# slave.net
KiCad netlist of a schematic drawn in EAGLE
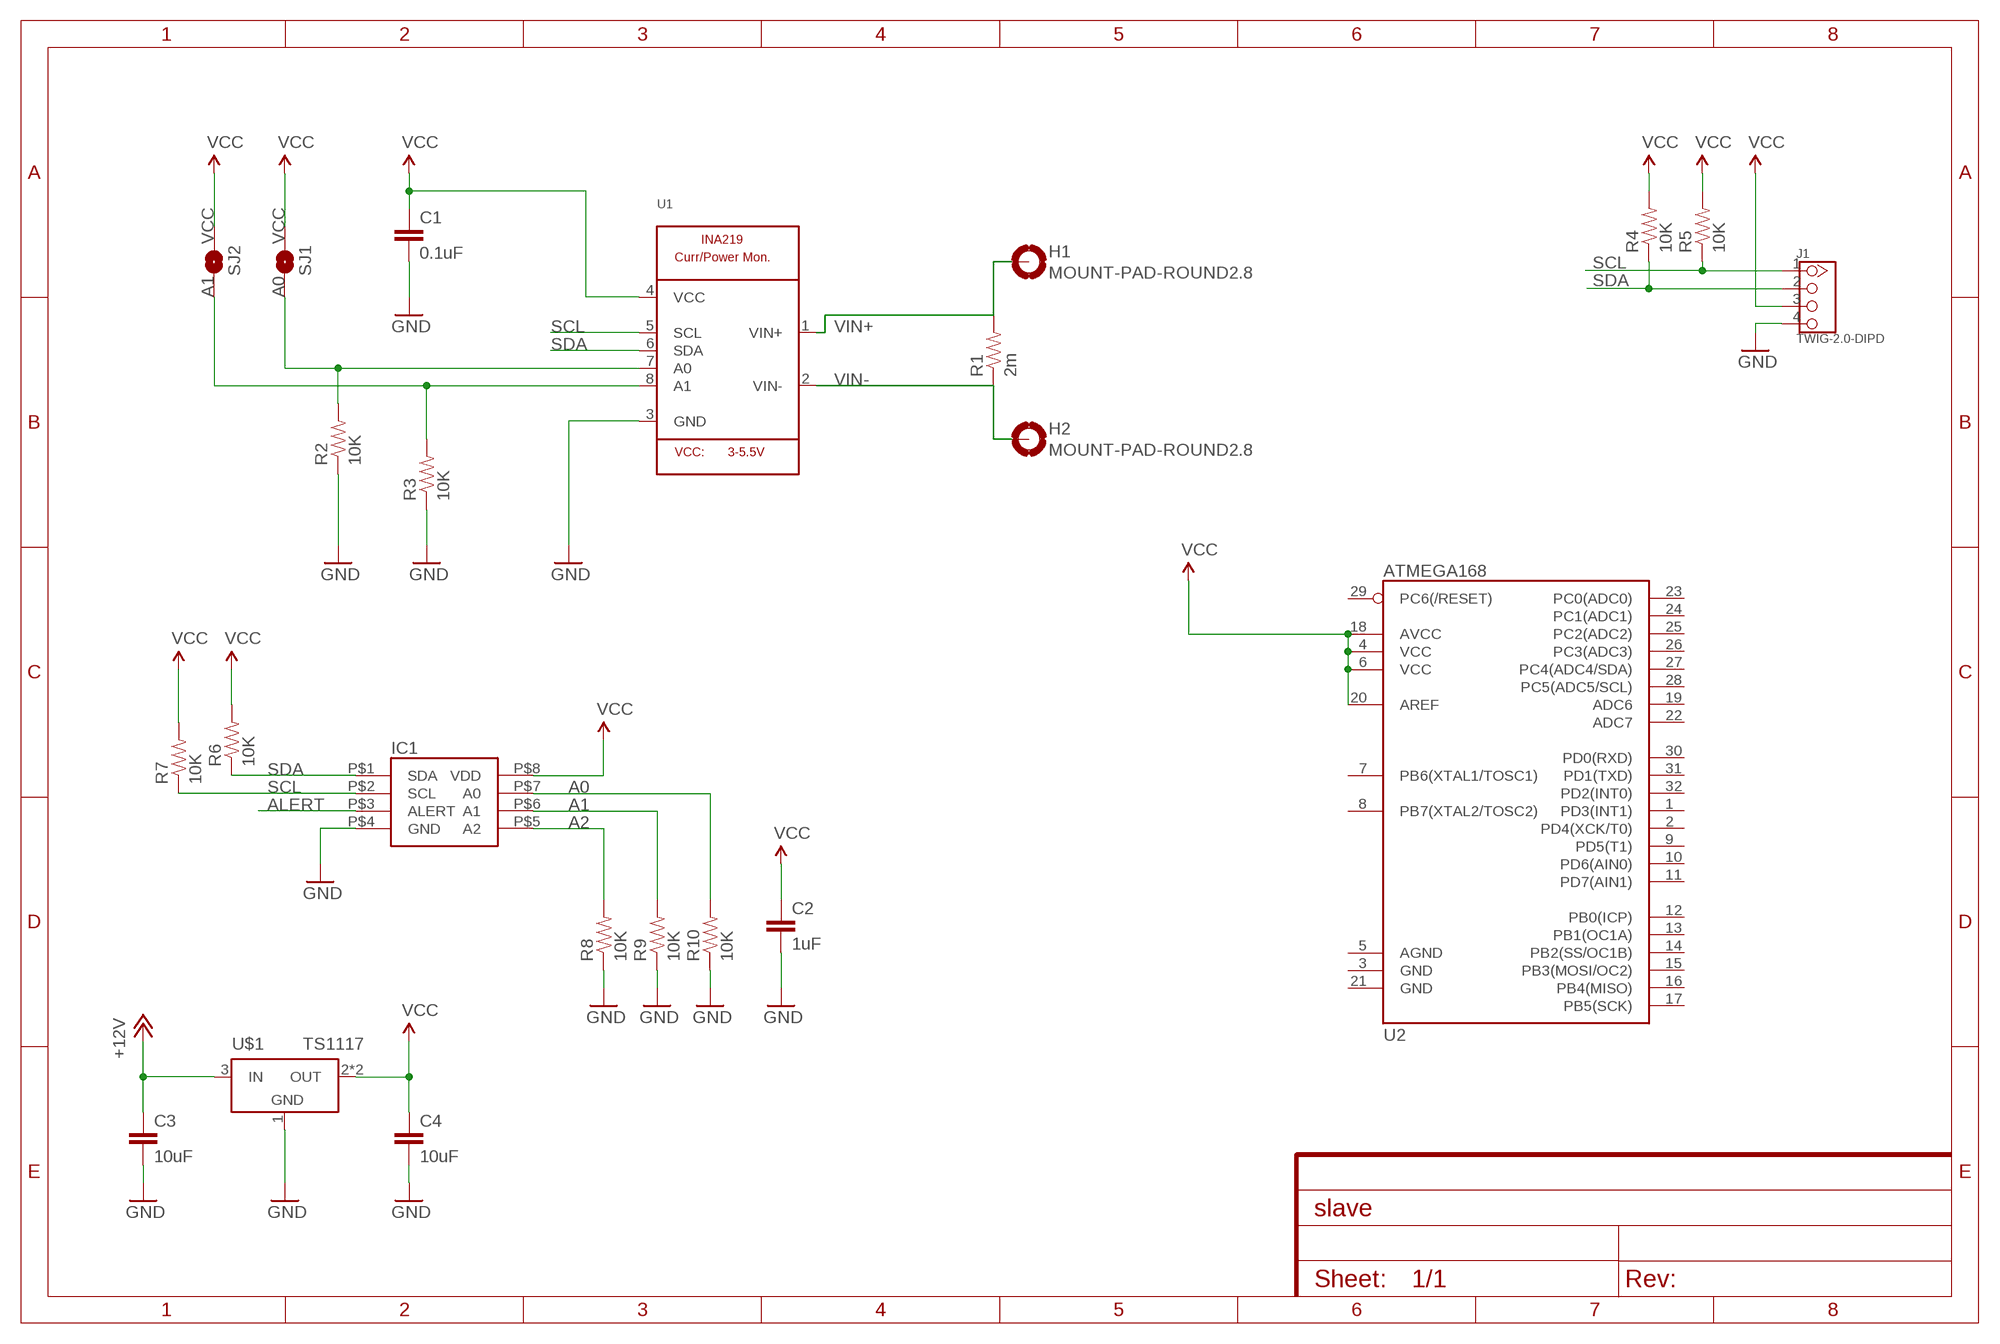
[diagram p0: schematic, sheet 1]

(export (version "E")
  (design (tool "Eeschema 10.0.6"))
  (components
    (comp (ref "C1")
      (value "0.1uF")
      (footprint "eagle-import:0805")
      (libsource (lib "eagle-import") (part "CAP0805"))
    )
    (comp (ref "C2")
      (value "1uF")
      (footprint "eagle-import:0805")
      (libsource (lib "eagle-import") (part "CAP0805"))
    )
    (comp (ref "C3")
      (value "10uF")
      (footprint "eagle-import:0805")
      (libsource (lib "eagle-import") (part "CAP0805"))
    )
    (comp (ref "C4")
      (value "10uF")
      (footprint "eagle-import:0805")
      (libsource (lib "eagle-import") (part "CAP0805"))
    )
    (comp (ref "H1")
      (value "MOUNT-PAD-ROUND2.8")
      (footprint "eagle-import:2,8-PAD")
      (libsource (lib "eagle-import") (part "MOUNT-PAD-ROUND2.8"))
    )
    (comp (ref "H2")
      (value "MOUNT-PAD-ROUND2.8")
      (footprint "eagle-import:2,8-PAD")
      (libsource (lib "eagle-import") (part "MOUNT-PAD-ROUND2.8"))
    )
    (comp (ref "IC1")
      (value "MPC9804")
      (footprint "eagle-import:MSOP-8")
      (libsource (lib "eagle-import") (part "MPC9804"))
    )
    (comp (ref "J1")
      (value "TWIG-2.0-DIPD")
      (footprint "eagle-import:2.0_1X4_90")
      (libsource (lib "eagle-import") (part "TWIG-2.0-DIPD"))
    )
    (comp (ref "R1")
      (value "2m")
      (footprint "eagle-import:R2512")
      (libsource (lib "eagle-import") (part "RESISTOR2512"))
    )
    (comp (ref "R2")
      (value "10K")
      (footprint "eagle-import:0805")
      (libsource (lib "eagle-import") (part "RESISTOR0805-RES"))
    )
    (comp (ref "R3")
      (value "10K")
      (footprint "eagle-import:0805")
      (libsource (lib "eagle-import") (part "RESISTOR0805-RES"))
    )
    (comp (ref "R4")
      (value "10K")
      (footprint "eagle-import:0805")
      (libsource (lib "eagle-import") (part "RESISTOR0805-RES"))
    )
    (comp (ref "R5")
      (value "10K")
      (footprint "eagle-import:0805")
      (libsource (lib "eagle-import") (part "RESISTOR0805-RES"))
    )
    (comp (ref "R6")
      (value "10K")
      (footprint "eagle-import:0805")
      (libsource (lib "eagle-import") (part "RESISTOR0805-RES"))
    )
    (comp (ref "R7")
      (value "10K")
      (footprint "eagle-import:0805")
      (libsource (lib "eagle-import") (part "RESISTOR0805-RES"))
    )
    (comp (ref "R8")
      (value "10K")
      (footprint "eagle-import:0805")
      (libsource (lib "eagle-import") (part "RESISTOR0805-RES"))
    )
    (comp (ref "R9")
      (value "10K")
      (footprint "eagle-import:0805")
      (libsource (lib "eagle-import") (part "RESISTOR0805-RES"))
    )
    (comp (ref "R10")
      (value "10K")
      (footprint "eagle-import:0805")
      (libsource (lib "eagle-import") (part "RESISTOR0805-RES"))
    )
    (comp (ref "SJ1")
      (value "SOLDERJUMPERNO")
      (footprint "eagle-import:SJ_2S-NO")
      (libsource (lib "eagle-import") (part "SOLDERJUMPERNO"))
    )
    (comp (ref "SJ2")
      (value "SOLDERJUMPERNO")
      (footprint "eagle-import:SJ_2S-NO")
      (libsource (lib "eagle-import") (part "SOLDERJUMPERNO"))
    )
    (comp (ref "U$1")
      (value "TS1117")
      (footprint "eagle-import:SOT223")
      (libsource (lib "eagle-import") (part "TS1117"))
    )
    (comp (ref "U1")
      (value "INA219")
      (footprint "eagle-import:SOT23-8")
      (libsource (lib "eagle-import") (part "INA219"))
    )
    (comp (ref "U2")
      (value "ATMEGA168")
      (footprint "eagle-import:TQFP32-08")
      (libsource (lib "eagle-import") (part "ATMEGA168"))
    )
  )
  (nets
    (net (code "1") (name "+12V") (class "Default")
      (node (ref "C3") (pin "1") (pinfunction "1_1") (pintype "passive"))
      (node (ref "U$1") (pin "3") (pinfunction "IN_3") (pintype "input"))
    )
    (net (code "2") (name "/A0") (class "Default")
      (node (ref "IC1") (pin "P$7") (pinfunction "A0_P$7") (pintype "input"))
      (node (ref "R10") (pin "2") (pinfunction "2_2") (pintype "passive"))
      (node (ref "R2") (pin "2") (pinfunction "2_2") (pintype "passive"))
      (node (ref "SJ1") (pin "1") (pinfunction "1_1") (pintype "passive"))
      (node (ref "U1") (pin "7") (pinfunction "A0_7") (pintype "bidirectional"))
    )
    (net (code "3") (name "/A1") (class "Default")
      (node (ref "IC1") (pin "P$6") (pinfunction "A1_P$6") (pintype "input"))
      (node (ref "R3") (pin "2") (pinfunction "2_2") (pintype "passive"))
      (node (ref "R9") (pin "2") (pinfunction "2_2") (pintype "passive"))
      (node (ref "SJ2") (pin "1") (pinfunction "1_1") (pintype "passive"))
      (node (ref "U1") (pin "8") (pinfunction "A1_8") (pintype "bidirectional"))
    )
    (net (code "4") (name "/A2") (class "Default")
      (node (ref "IC1") (pin "P$5") (pinfunction "A2_P$5") (pintype "input"))
      (node (ref "R8") (pin "2") (pinfunction "2_2") (pintype "passive"))
    )
    (net (code "5") (name "/ALERT") (class "Default")
      (node (ref "IC1") (pin "P$3") (pinfunction "ALERT_P$3") (pintype "output"))
    )
    (net (code "6") (name "/SCL") (class "Default")
      (node (ref "IC1") (pin "P$2") (pinfunction "SCL_P$2") (pintype "output"))
      (node (ref "J1") (pin "1") (pinfunction "1_1") (pintype "bidirectional"))
      (node (ref "R5") (pin "1") (pinfunction "1_1") (pintype "passive"))
      (node (ref "R7") (pin "1") (pinfunction "1_1") (pintype "passive"))
      (node (ref "U1") (pin "5") (pinfunction "SCL_5") (pintype "bidirectional"))
    )
    (net (code "7") (name "/SDA") (class "Default")
      (node (ref "IC1") (pin "P$1") (pinfunction "SDA_P$1") (pintype "bidirectional"))
      (node (ref "J1") (pin "2") (pinfunction "2_2") (pintype "bidirectional"))
      (node (ref "R4") (pin "1") (pinfunction "1_1") (pintype "passive"))
      (node (ref "R6") (pin "1") (pinfunction "1_1") (pintype "passive"))
      (node (ref "U1") (pin "6") (pinfunction "SDA_6") (pintype "bidirectional"))
    )
    (net (code "8") (name "/VIN+") (class "Default")
      (node (ref "H1") (pin "B2,8") (pinfunction "MOUNT_B2,8") (pintype "passive"))
      (node (ref "R1") (pin "2") (pinfunction "2_2") (pintype "passive"))
      (node (ref "U1") (pin "1") (pinfunction "VIN+_1") (pintype "bidirectional"))
    )
    (net (code "9") (name "/VIN-") (class "Default")
      (node (ref "H2") (pin "B2,8") (pinfunction "MOUNT_B2,8") (pintype "passive"))
      (node (ref "R1") (pin "1") (pinfunction "1_1") (pintype "passive"))
      (node (ref "U1") (pin "2") (pinfunction "VIN-_2") (pintype "bidirectional"))
    )
    (net (code "10") (name "GND") (class "Default")
      (node (ref "C1") (pin "2") (pinfunction "2_2") (pintype "passive"))
      (node (ref "C2") (pin "2") (pinfunction "2_2") (pintype "passive"))
      (node (ref "C3") (pin "2") (pinfunction "2_2") (pintype "passive"))
      (node (ref "C4") (pin "2") (pinfunction "2_2") (pintype "passive"))
      (node (ref "IC1") (pin "P$4") (pinfunction "GND_P$4") (pintype "power_in"))
      (node (ref "J1") (pin "4") (pinfunction "4_4") (pintype "bidirectional"))
      (node (ref "R10") (pin "1") (pinfunction "1_1") (pintype "passive"))
      (node (ref "R2") (pin "1") (pinfunction "1_1") (pintype "passive"))
      (node (ref "R3") (pin "1") (pinfunction "1_1") (pintype "passive"))
      (node (ref "R8") (pin "1") (pinfunction "1_1") (pintype "passive"))
      (node (ref "R9") (pin "1") (pinfunction "1_1") (pintype "passive"))
      (node (ref "U$1") (pin "1") (pinfunction "GND_1") (pintype "power_in"))
      (node (ref "U1") (pin "3") (pinfunction "GND_3") (pintype "bidirectional"))
    )
    (net (code "11") (name "VCC") (class "Default")
      (node (ref "C1") (pin "1") (pinfunction "1_1") (pintype "passive"))
      (node (ref "C2") (pin "1") (pinfunction "1_1") (pintype "passive"))
      (node (ref "C4") (pin "1") (pinfunction "1_1") (pintype "passive"))
      (node (ref "IC1") (pin "P$8") (pinfunction "VDD_P$8") (pintype "power_in"))
      (node (ref "J1") (pin "3") (pinfunction "3_3") (pintype "bidirectional"))
      (node (ref "R4") (pin "2") (pinfunction "2_2") (pintype "passive"))
      (node (ref "R5") (pin "2") (pinfunction "2_2") (pintype "passive"))
      (node (ref "R6") (pin "2") (pinfunction "2_2") (pintype "passive"))
      (node (ref "R7") (pin "2") (pinfunction "2_2") (pintype "passive"))
      (node (ref "SJ1") (pin "2") (pinfunction "2_2") (pintype "passive"))
      (node (ref "SJ2") (pin "2") (pinfunction "2_2") (pintype "passive"))
      (node (ref "U$1") (pin "2") (pinfunction "OUT_2") (pintype "output"))
      (node (ref "U$1") (pin "4") (pinfunction "OUT_4") (pintype "output"))
      (node (ref "U1") (pin "4") (pinfunction "VCC_4") (pintype "bidirectional"))
      (node (ref "U2") (pin "18") (pinfunction "AVCC_18") (pintype "bidirectional"))
      (node (ref "U2") (pin "20") (pinfunction "AREF_20") (pintype "bidirectional"))
      (node (ref "U2") (pin "4") (pinfunction "VCC_4") (pintype "bidirectional"))
      (node (ref "U2") (pin "6") (pinfunction "VCC_6") (pintype "bidirectional"))
    )
    (net (code "12") (name "unconnected-(U2-ADC6-Pad19)") (class "Default")
      (node (ref "U2") (pin "19") (pinfunction "ADC6_19") (pintype "bidirectional"))
    )
    (net (code "13") (name "unconnected-(U2-ADC7-Pad22)") (class "Default")
      (node (ref "U2") (pin "22") (pinfunction "ADC7_22") (pintype "bidirectional"))
    )
    (net (code "14") (name "unconnected-(U2-AGND-Pad5)") (class "Default")
      (node (ref "U2") (pin "5") (pinfunction "AGND_5") (pintype "bidirectional"))
    )
    (net (code "15") (name "unconnected-(U2-GND-Pad3)") (class "Default")
      (node (ref "U2") (pin "3") (pinfunction "GND_3") (pintype "bidirectional"))
    )
    (net (code "16") (name "unconnected-(U2-GND-Pad21)") (class "Default")
      (node (ref "U2") (pin "21") (pinfunction "GND_21") (pintype "bidirectional"))
    )
    (net (code "17") (name "unconnected-(U2-PB0(ICP)-Pad12)") (class "Default")
      (node (ref "U2") (pin "12") (pinfunction "PB0(ICP)_12") (pintype "bidirectional"))
    )
    (net (code "18") (name "unconnected-(U2-PB1(OC1A)-Pad13)") (class "Default")
      (node (ref "U2") (pin "13") (pinfunction "PB1(OC1A)_13") (pintype "bidirectional"))
    )
    (net (code "19") (name "unconnected-(U2-PB2(SS{slash}OC1B)-Pad14)") (class "Default")
      (node (ref "U2") (pin "14") (pinfunction "PB2(SS/OC1B)_14") (pintype "bidirectional"))
    )
    (net (code "20") (name "unconnected-(U2-PB3(MOSI{slash}OC2)-Pad15)") (class "Default")
      (node (ref "U2") (pin "15") (pinfunction "PB3(MOSI/OC2)_15") (pintype "bidirectional"))
    )
    (net (code "21") (name "unconnected-(U2-PB4(MISO)-Pad16)") (class "Default")
      (node (ref "U2") (pin "16") (pinfunction "PB4(MISO)_16") (pintype "bidirectional"))
    )
    (net (code "22") (name "unconnected-(U2-PB5(SCK)-Pad17)") (class "Default")
      (node (ref "U2") (pin "17") (pinfunction "PB5(SCK)_17") (pintype "bidirectional"))
    )
    (net (code "23") (name "unconnected-(U2-PB6(XTAL1{slash}TOSC1)-Pad7)") (class "Default")
      (node (ref "U2") (pin "7") (pinfunction "PB6(XTAL1/TOSC1)_7") (pintype "bidirectional"))
    )
    (net (code "24") (name "unconnected-(U2-PB7(XTAL2{slash}TOSC2)-Pad8)") (class "Default")
      (node (ref "U2") (pin "8") (pinfunction "PB7(XTAL2/TOSC2)_8") (pintype "bidirectional"))
    )
    (net (code "25") (name "unconnected-(U2-PC0(ADC0)-Pad23)") (class "Default")
      (node (ref "U2") (pin "23") (pinfunction "PC0(ADC0)_23") (pintype "bidirectional"))
    )
    (net (code "26") (name "unconnected-(U2-PC1(ADC1)-Pad24)") (class "Default")
      (node (ref "U2") (pin "24") (pinfunction "PC1(ADC1)_24") (pintype "bidirectional"))
    )
    (net (code "27") (name "unconnected-(U2-PC2(ADC2)-Pad25)") (class "Default")
      (node (ref "U2") (pin "25") (pinfunction "PC2(ADC2)_25") (pintype "bidirectional"))
    )
    (net (code "28") (name "unconnected-(U2-PC3(ADC3)-Pad26)") (class "Default")
      (node (ref "U2") (pin "26") (pinfunction "PC3(ADC3)_26") (pintype "bidirectional"))
    )
    (net (code "29") (name "unconnected-(U2-PC4(ADC4{slash}SDA)-Pad27)") (class "Default")
      (node (ref "U2") (pin "27") (pinfunction "PC4(ADC4/SDA)_27") (pintype "bidirectional"))
    )
    (net (code "30") (name "unconnected-(U2-PC5(ADC5{slash}SCL)-Pad28)") (class "Default")
      (node (ref "U2") (pin "28") (pinfunction "PC5(ADC5/SCL)_28") (pintype "bidirectional"))
    )
    (net (code "31") (name "unconnected-(U2-PC6({slash}RESET)-Pad29)") (class "Default")
      (node (ref "U2") (pin "29") (pinfunction "PC6(/RESET)_29") (pintype "bidirectional"))
    )
    (net (code "32") (name "unconnected-(U2-PD0(RXD)-Pad30)") (class "Default")
      (node (ref "U2") (pin "30") (pinfunction "PD0(RXD)_30") (pintype "bidirectional"))
    )
    (net (code "33") (name "unconnected-(U2-PD1(TXD)-Pad31)") (class "Default")
      (node (ref "U2") (pin "31") (pinfunction "PD1(TXD)_31") (pintype "bidirectional"))
    )
    (net (code "34") (name "unconnected-(U2-PD2(INT0)-Pad32)") (class "Default")
      (node (ref "U2") (pin "32") (pinfunction "PD2(INT0)_32") (pintype "bidirectional"))
    )
    (net (code "35") (name "unconnected-(U2-PD3(INT1)-Pad1)") (class "Default")
      (node (ref "U2") (pin "1") (pinfunction "PD3(INT1)_1") (pintype "bidirectional"))
    )
    (net (code "36") (name "unconnected-(U2-PD4(XCK{slash}T0)-Pad2)") (class "Default")
      (node (ref "U2") (pin "2") (pinfunction "PD4(XCK/T0)_2") (pintype "bidirectional"))
    )
    (net (code "37") (name "unconnected-(U2-PD5(T1)-Pad9)") (class "Default")
      (node (ref "U2") (pin "9") (pinfunction "PD5(T1)_9") (pintype "bidirectional"))
    )
    (net (code "38") (name "unconnected-(U2-PD6(AIN0)-Pad10)") (class "Default")
      (node (ref "U2") (pin "10") (pinfunction "PD6(AIN0)_10") (pintype "bidirectional"))
    )
    (net (code "39") (name "unconnected-(U2-PD7(AIN1)-Pad11)") (class "Default")
      (node (ref "U2") (pin "11") (pinfunction "PD7(AIN1)_11") (pintype "bidirectional"))
    )
  )
)
